# TSSP.net
KiCad netlist of a schematic drawn in Altium Designer
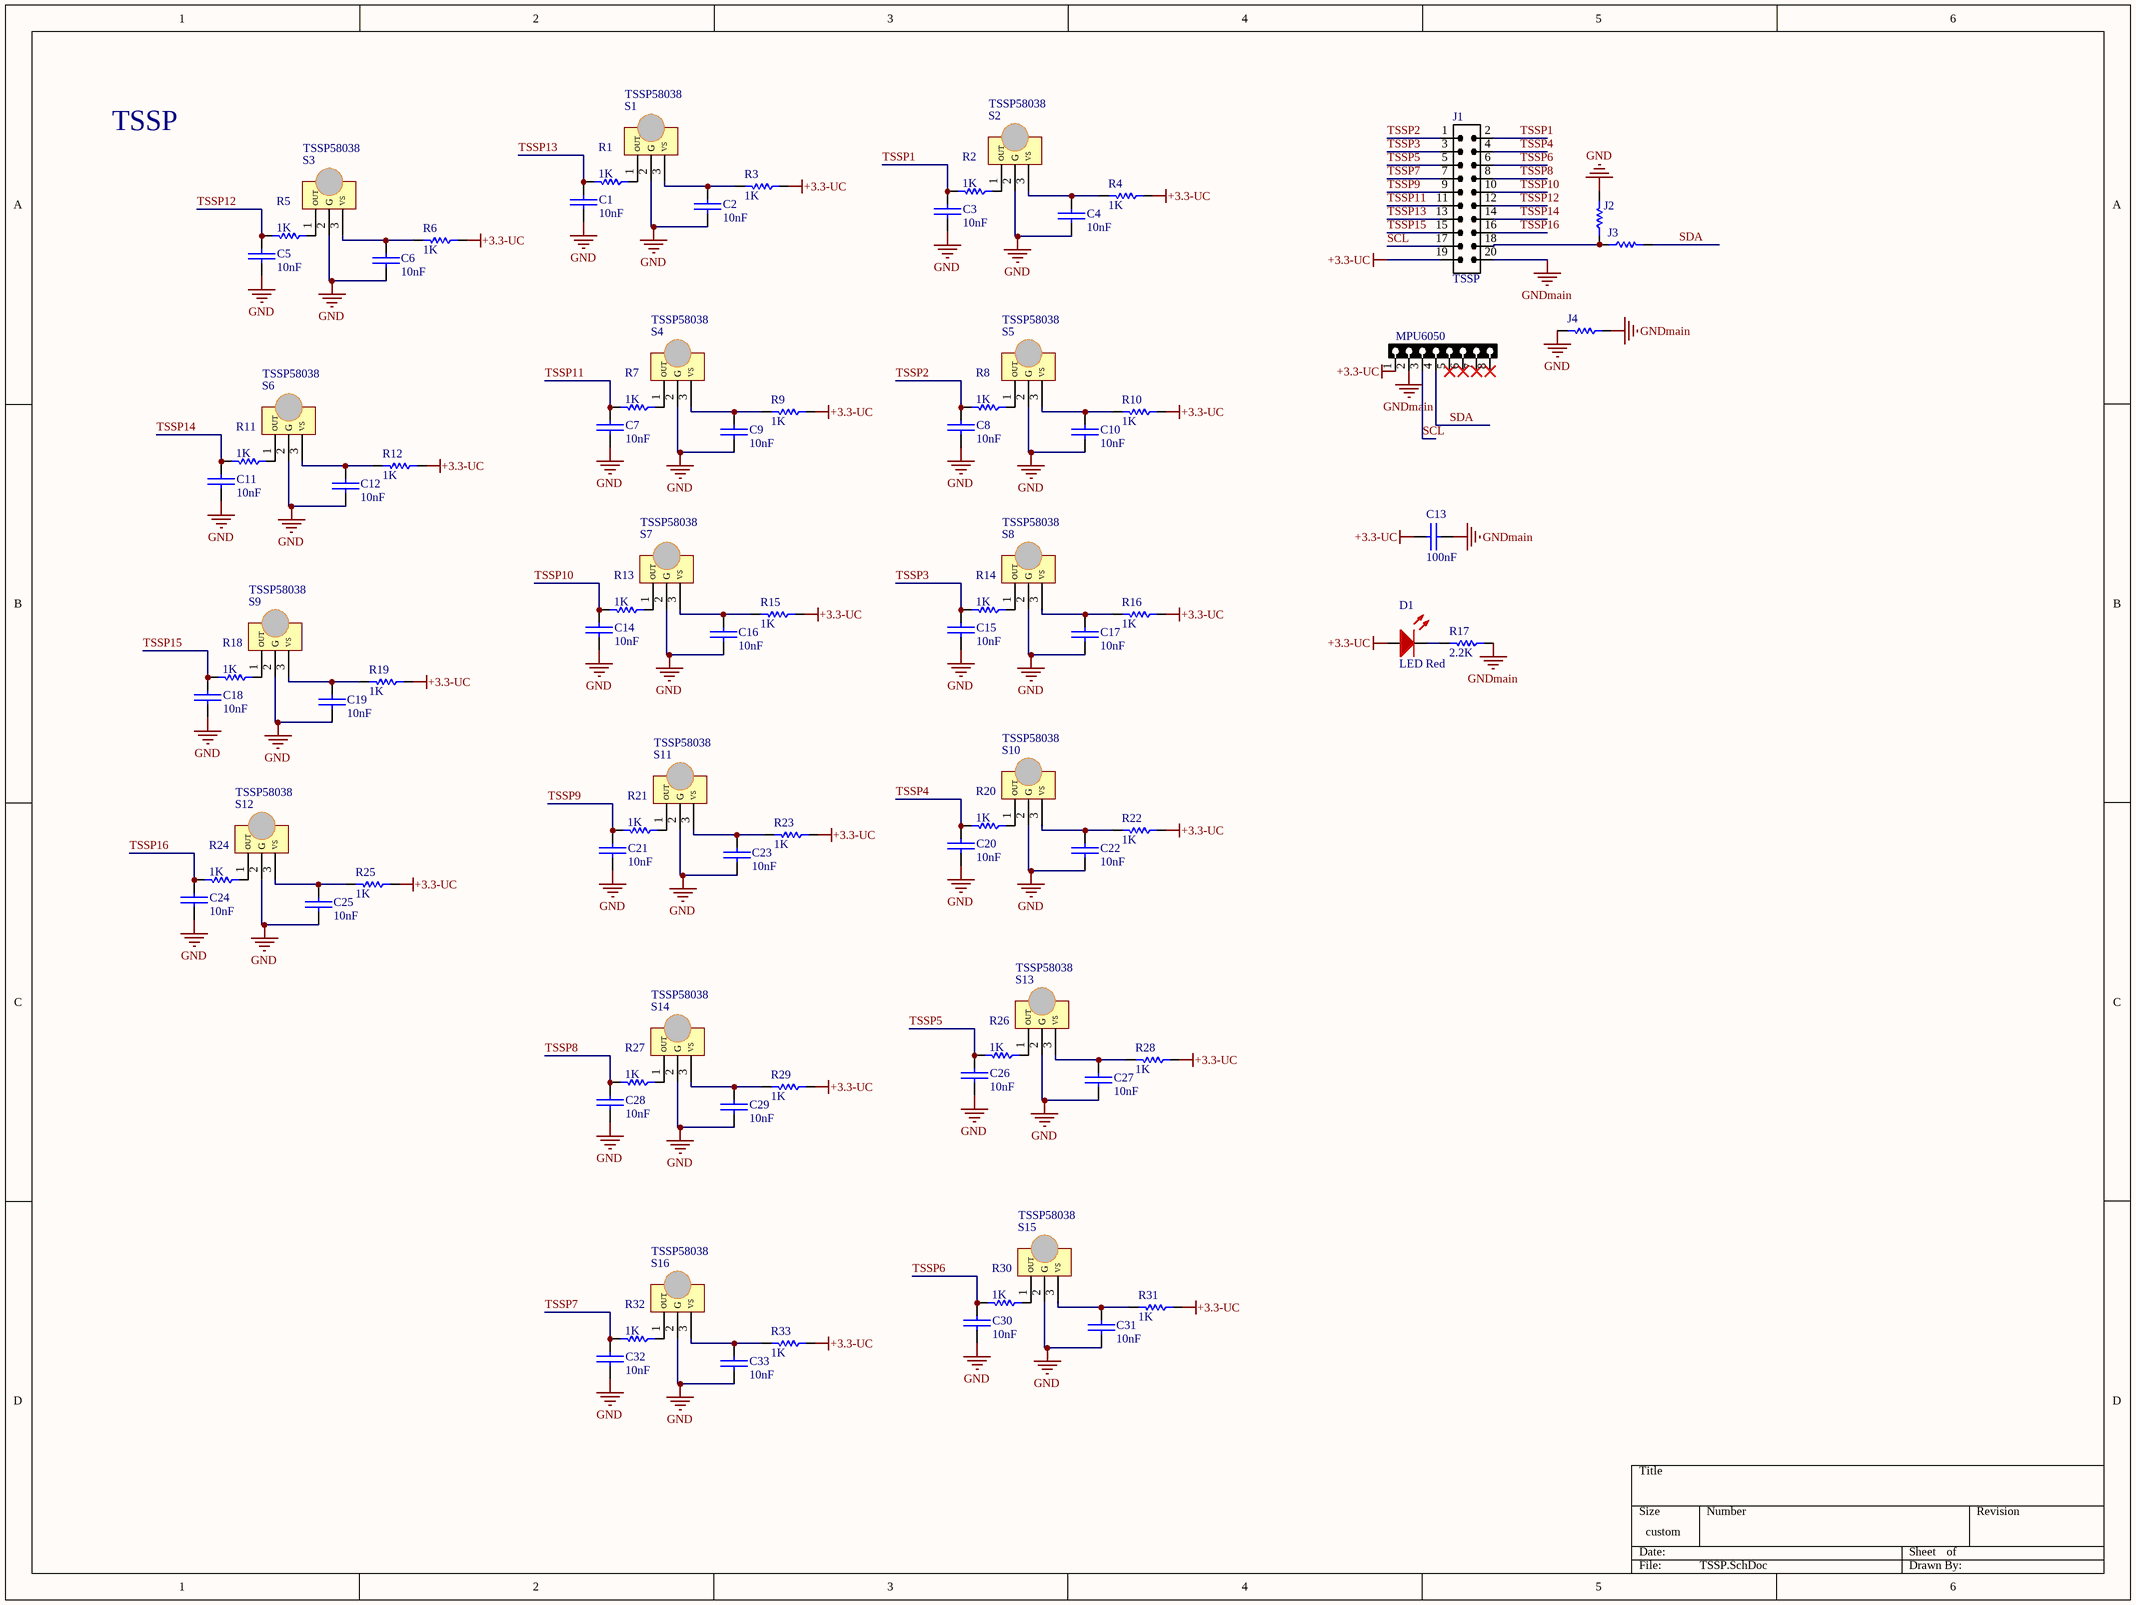
[diagram p0: TSSP.SchDoc]

(export (version "E")
  (design (tool "Eeschema 10.0.6"))
  (components
    (comp (ref "C1")
      (value "10nF")
      (footprint "C0603")
      (description "Bipolar Capacitor")
      (fields (field (name "VOLTAGE") "100V") (field (name "DESIGNER") "Saeid Jorablo"))
      (libsource (lib "My Library") (part "Cap-Bipolar"))
    )
    (comp (ref "C2")
      (value "10nF")
      (footprint "C0603")
      (description "Bipolar Capacitor")
      (fields (field (name "VOLTAGE") "100V") (field (name "DESIGNER") "Saeid Jorablo"))
      (libsource (lib "My Library") (part "Cap-Bipolar"))
    )
    (comp (ref "C3")
      (value "10nF")
      (footprint "C0603")
      (description "Bipolar Capacitor")
      (fields (field (name "VOLTAGE") "100V") (field (name "DESIGNER") "Saeid Jorablo"))
      (libsource (lib "My Library") (part "Cap-Bipolar"))
    )
    (comp (ref "C4")
      (value "10nF")
      (footprint "C0603")
      (description "Bipolar Capacitor")
      (fields (field (name "VOLTAGE") "100V") (field (name "DESIGNER") "Saeid Jorablo"))
      (libsource (lib "My Library") (part "Cap-Bipolar"))
    )
    (comp (ref "C5")
      (value "10nF")
      (footprint "C0603")
      (description "Bipolar Capacitor")
      (fields (field (name "VOLTAGE") "100V") (field (name "DESIGNER") "Saeid Jorablo"))
      (libsource (lib "My Library") (part "Cap-Bipolar"))
    )
    (comp (ref "C6")
      (value "10nF")
      (footprint "C0603")
      (description "Bipolar Capacitor")
      (fields (field (name "VOLTAGE") "100V") (field (name "DESIGNER") "Saeid Jorablo"))
      (libsource (lib "My Library") (part "Cap-Bipolar"))
    )
    (comp (ref "C7")
      (value "10nF")
      (footprint "C0603")
      (description "Bipolar Capacitor")
      (fields (field (name "VOLTAGE") "100V") (field (name "DESIGNER") "Saeid Jorablo"))
      (libsource (lib "My Library") (part "Cap-Bipolar"))
    )
    (comp (ref "C8")
      (value "10nF")
      (footprint "C0603")
      (description "Bipolar Capacitor")
      (fields (field (name "VOLTAGE") "100V") (field (name "DESIGNER") "Saeid Jorablo"))
      (libsource (lib "My Library") (part "Cap-Bipolar"))
    )
    (comp (ref "C9")
      (value "10nF")
      (footprint "C0603")
      (description "Bipolar Capacitor")
      (fields (field (name "VOLTAGE") "100V") (field (name "DESIGNER") "Saeid Jorablo"))
      (libsource (lib "My Library") (part "Cap-Bipolar"))
    )
    (comp (ref "C10")
      (value "10nF")
      (footprint "C0603")
      (description "Bipolar Capacitor")
      (fields (field (name "VOLTAGE") "100V") (field (name "DESIGNER") "Saeid Jorablo"))
      (libsource (lib "My Library") (part "Cap-Bipolar"))
    )
    (comp (ref "C11")
      (value "10nF")
      (footprint "C0603")
      (description "Bipolar Capacitor")
      (fields (field (name "VOLTAGE") "100V") (field (name "DESIGNER") "Saeid Jorablo"))
      (libsource (lib "My Library") (part "Cap-Bipolar"))
    )
    (comp (ref "C12")
      (value "10nF")
      (footprint "C0603")
      (description "Bipolar Capacitor")
      (fields (field (name "VOLTAGE") "100V") (field (name "DESIGNER") "Saeid Jorablo"))
      (libsource (lib "My Library") (part "Cap-Bipolar"))
    )
    (comp (ref "C13")
      (value "100nF")
      (footprint "SMD_CAP_0805")
      (description "Bipolar Capacitor")
      (fields (field (name "VOLTAGE") "100V") (field (name "DESIGNER") "Saeid Jorablo"))
      (libsource (lib "My Library") (part "Cap-Bipolar"))
    )
    (comp (ref "C14")
      (value "10nF")
      (footprint "C0603")
      (description "Bipolar Capacitor")
      (fields (field (name "VOLTAGE") "100V") (field (name "DESIGNER") "Saeid Jorablo"))
      (libsource (lib "My Library") (part "Cap-Bipolar"))
    )
    (comp (ref "C15")
      (value "10nF")
      (footprint "C0603")
      (description "Bipolar Capacitor")
      (fields (field (name "VOLTAGE") "100V") (field (name "DESIGNER") "Saeid Jorablo"))
      (libsource (lib "My Library") (part "Cap-Bipolar"))
    )
    (comp (ref "C16")
      (value "10nF")
      (footprint "C0603")
      (description "Bipolar Capacitor")
      (fields (field (name "VOLTAGE") "100V") (field (name "DESIGNER") "Saeid Jorablo"))
      (libsource (lib "My Library") (part "Cap-Bipolar"))
    )
    (comp (ref "C17")
      (value "10nF")
      (footprint "C0603")
      (description "Bipolar Capacitor")
      (fields (field (name "VOLTAGE") "100V") (field (name "DESIGNER") "Saeid Jorablo"))
      (libsource (lib "My Library") (part "Cap-Bipolar"))
    )
    (comp (ref "C18")
      (value "10nF")
      (footprint "C0603")
      (description "Bipolar Capacitor")
      (fields (field (name "VOLTAGE") "100V") (field (name "DESIGNER") "Saeid Jorablo"))
      (libsource (lib "My Library") (part "Cap-Bipolar"))
    )
    (comp (ref "C19")
      (value "10nF")
      (footprint "C0603")
      (description "Bipolar Capacitor")
      (fields (field (name "VOLTAGE") "100V") (field (name "DESIGNER") "Saeid Jorablo"))
      (libsource (lib "My Library") (part "Cap-Bipolar"))
    )
    (comp (ref "C20")
      (value "10nF")
      (footprint "C0603")
      (description "Bipolar Capacitor")
      (fields (field (name "VOLTAGE") "100V") (field (name "DESIGNER") "Saeid Jorablo"))
      (libsource (lib "My Library") (part "Cap-Bipolar"))
    )
    (comp (ref "C21")
      (value "10nF")
      (footprint "C0603")
      (description "Bipolar Capacitor")
      (fields (field (name "VOLTAGE") "100V") (field (name "DESIGNER") "Saeid Jorablo"))
      (libsource (lib "My Library") (part "Cap-Bipolar"))
    )
    (comp (ref "C22")
      (value "10nF")
      (footprint "C0603")
      (description "Bipolar Capacitor")
      (fields (field (name "VOLTAGE") "100V") (field (name "DESIGNER") "Saeid Jorablo"))
      (libsource (lib "My Library") (part "Cap-Bipolar"))
    )
    (comp (ref "C23")
      (value "10nF")
      (footprint "C0603")
      (description "Bipolar Capacitor")
      (fields (field (name "VOLTAGE") "100V") (field (name "DESIGNER") "Saeid Jorablo"))
      (libsource (lib "My Library") (part "Cap-Bipolar"))
    )
    (comp (ref "C24")
      (value "10nF")
      (footprint "C0603")
      (description "Bipolar Capacitor")
      (fields (field (name "VOLTAGE") "100V") (field (name "DESIGNER") "Saeid Jorablo"))
      (libsource (lib "My Library") (part "Cap-Bipolar"))
    )
    (comp (ref "C25")
      (value "10nF")
      (footprint "C0603")
      (description "Bipolar Capacitor")
      (fields (field (name "VOLTAGE") "100V") (field (name "DESIGNER") "Saeid Jorablo"))
      (libsource (lib "My Library") (part "Cap-Bipolar"))
    )
    (comp (ref "C26")
      (value "10nF")
      (footprint "C0603")
      (description "Bipolar Capacitor")
      (fields (field (name "VOLTAGE") "100V") (field (name "DESIGNER") "Saeid Jorablo"))
      (libsource (lib "My Library") (part "Cap-Bipolar"))
    )
    (comp (ref "C27")
      (value "10nF")
      (footprint "C0603")
      (description "Bipolar Capacitor")
      (fields (field (name "VOLTAGE") "100V") (field (name "DESIGNER") "Saeid Jorablo"))
      (libsource (lib "My Library") (part "Cap-Bipolar"))
    )
    (comp (ref "C28")
      (value "10nF")
      (footprint "C0603")
      (description "Bipolar Capacitor")
      (fields (field (name "VOLTAGE") "100V") (field (name "DESIGNER") "Saeid Jorablo"))
      (libsource (lib "My Library") (part "Cap-Bipolar"))
    )
    (comp (ref "C29")
      (value "10nF")
      (footprint "C0603")
      (description "Bipolar Capacitor")
      (fields (field (name "VOLTAGE") "100V") (field (name "DESIGNER") "Saeid Jorablo"))
      (libsource (lib "My Library") (part "Cap-Bipolar"))
    )
    (comp (ref "C30")
      (value "10nF")
      (footprint "C0603")
      (description "Bipolar Capacitor")
      (fields (field (name "VOLTAGE") "100V") (field (name "DESIGNER") "Saeid Jorablo"))
      (libsource (lib "My Library") (part "Cap-Bipolar"))
    )
    (comp (ref "C31")
      (value "10nF")
      (footprint "C0603")
      (description "Bipolar Capacitor")
      (fields (field (name "VOLTAGE") "100V") (field (name "DESIGNER") "Saeid Jorablo"))
      (libsource (lib "My Library") (part "Cap-Bipolar"))
    )
    (comp (ref "C32")
      (value "10nF")
      (footprint "C0603")
      (description "Bipolar Capacitor")
      (fields (field (name "VOLTAGE") "100V") (field (name "DESIGNER") "Saeid Jorablo"))
      (libsource (lib "My Library") (part "Cap-Bipolar"))
    )
    (comp (ref "C33")
      (value "10nF")
      (footprint "C0603")
      (description "Bipolar Capacitor")
      (fields (field (name "VOLTAGE") "100V") (field (name "DESIGNER") "Saeid Jorablo"))
      (libsource (lib "My Library") (part "Cap-Bipolar"))
    )
    (comp (ref "D1")
      (value "LED Red")
      (footprint "LED_Red_1206")
      (libsource (lib "AYRIC Library") (part "LED Red"))
    )
    (comp (ref "J1")
      (value "TSSP")
      (footprint "IDC_2X10")
      (description "CONN, IDC, Male, pitch: 2.54mm, 20POS")
      (libsource (lib "conn_header_idc") (part "IDC_2X10"))
    )
    (comp (ref "J2")
      (value "~")
      (footprint "RES 0805 (2012X06L)")
      (description "Resistor")
      (libsource (lib "My Library") (part "Resistor"))
    )
    (comp (ref "J3")
      (value "~")
      (footprint "RES 0805 (2012X06L)")
      (description "Resistor")
      (libsource (lib "My Library") (part "Resistor"))
    )
    (comp (ref "J4")
      (value "~")
      (footprint "RES 0805 (2012X06L)")
      (description "Resistor")
      (libsource (lib "My Library") (part "Resistor"))
    )
    (comp (ref "MPU6050")
      (value "HDRF8")
      (footprint "HDR_F_1X8")
      (description "CONN, HEADER, Female, pitch: 2.54mm, 8POS")
      (libsource (lib "conn_header") (part "HDR_F_1X8"))
    )
    (comp (ref "R1")
      (value "1K")
      (footprint "RES 0603 (1608X06L)")
      (description "Resistor")
      (libsource (lib "My Library") (part "Resistor"))
    )
    (comp (ref "R2")
      (value "1K")
      (footprint "RES 0603 (1608X06L)")
      (description "Resistor")
      (libsource (lib "My Library") (part "Resistor"))
    )
    (comp (ref "R3")
      (value "1K")
      (footprint "RES 0603 (1608X06L)")
      (description "Resistor")
      (libsource (lib "My Library") (part "Resistor"))
    )
    (comp (ref "R4")
      (value "1K")
      (footprint "RES 0603 (1608X06L)")
      (description "Resistor")
      (libsource (lib "My Library") (part "Resistor"))
    )
    (comp (ref "R5")
      (value "1K")
      (footprint "RES 0603 (1608X06L)")
      (description "Resistor")
      (libsource (lib "My Library") (part "Resistor"))
    )
    (comp (ref "R6")
      (value "1K")
      (footprint "RES 0603 (1608X06L)")
      (description "Resistor")
      (libsource (lib "My Library") (part "Resistor"))
    )
    (comp (ref "R7")
      (value "1K")
      (footprint "RES 0603 (1608X06L)")
      (description "Resistor")
      (libsource (lib "My Library") (part "Resistor"))
    )
    (comp (ref "R8")
      (value "1K")
      (footprint "RES 0603 (1608X06L)")
      (description "Resistor")
      (libsource (lib "My Library") (part "Resistor"))
    )
    (comp (ref "R9")
      (value "1K")
      (footprint "RES 0603 (1608X06L)")
      (description "Resistor")
      (libsource (lib "My Library") (part "Resistor"))
    )
    (comp (ref "R10")
      (value "1K")
      (footprint "RES 0603 (1608X06L)")
      (description "Resistor")
      (libsource (lib "My Library") (part "Resistor"))
    )
    (comp (ref "R11")
      (value "1K")
      (footprint "RES 0603 (1608X06L)")
      (description "Resistor")
      (libsource (lib "My Library") (part "Resistor"))
    )
    (comp (ref "R12")
      (value "1K")
      (footprint "RES 0603 (1608X06L)")
      (description "Resistor")
      (libsource (lib "My Library") (part "Resistor"))
    )
    (comp (ref "R13")
      (value "1K")
      (footprint "RES 0603 (1608X06L)")
      (description "Resistor")
      (libsource (lib "My Library") (part "Resistor"))
    )
    (comp (ref "R14")
      (value "1K")
      (footprint "RES 0603 (1608X06L)")
      (description "Resistor")
      (libsource (lib "My Library") (part "Resistor"))
    )
    (comp (ref "R15")
      (value "1K")
      (footprint "RES 0603 (1608X06L)")
      (description "Resistor")
      (libsource (lib "My Library") (part "Resistor"))
    )
    (comp (ref "R16")
      (value "1K")
      (footprint "RES 0603 (1608X06L)")
      (description "Resistor")
      (libsource (lib "My Library") (part "Resistor"))
    )
    (comp (ref "R17")
      (value "2.2K")
      (footprint "RES 0805 (2012X06L)")
      (description "Resistor")
      (libsource (lib "My Library") (part "Resistor"))
    )
    (comp (ref "R18")
      (value "1K")
      (footprint "RES 0603 (1608X06L)")
      (description "Resistor")
      (libsource (lib "My Library") (part "Resistor"))
    )
    (comp (ref "R19")
      (value "1K")
      (footprint "RES 0603 (1608X06L)")
      (description "Resistor")
      (libsource (lib "My Library") (part "Resistor"))
    )
    (comp (ref "R20")
      (value "1K")
      (footprint "RES 0603 (1608X06L)")
      (description "Resistor")
      (libsource (lib "My Library") (part "Resistor"))
    )
    (comp (ref "R21")
      (value "1K")
      (footprint "RES 0603 (1608X06L)")
      (description "Resistor")
      (libsource (lib "My Library") (part "Resistor"))
    )
    (comp (ref "R22")
      (value "1K")
      (footprint "RES 0603 (1608X06L)")
      (description "Resistor")
      (libsource (lib "My Library") (part "Resistor"))
    )
    (comp (ref "R23")
      (value "1K")
      (footprint "RES 0603 (1608X06L)")
      (description "Resistor")
      (libsource (lib "My Library") (part "Resistor"))
    )
    (comp (ref "R24")
      (value "1K")
      (footprint "RES 0603 (1608X06L)")
      (description "Resistor")
      (libsource (lib "My Library") (part "Resistor"))
    )
    (comp (ref "R25")
      (value "1K")
      (footprint "RES 0603 (1608X06L)")
      (description "Resistor")
      (libsource (lib "My Library") (part "Resistor"))
    )
    (comp (ref "R26")
      (value "1K")
      (footprint "RES 0603 (1608X06L)")
      (description "Resistor")
      (libsource (lib "My Library") (part "Resistor"))
    )
    (comp (ref "R27")
      (value "1K")
      (footprint "RES 0603 (1608X06L)")
      (description "Resistor")
      (libsource (lib "My Library") (part "Resistor"))
    )
    (comp (ref "R28")
      (value "1K")
      (footprint "RES 0603 (1608X06L)")
      (description "Resistor")
      (libsource (lib "My Library") (part "Resistor"))
    )
    (comp (ref "R29")
      (value "1K")
      (footprint "RES 0603 (1608X06L)")
      (description "Resistor")
      (libsource (lib "My Library") (part "Resistor"))
    )
    (comp (ref "R30")
      (value "1K")
      (footprint "RES 0603 (1608X06L)")
      (description "Resistor")
      (libsource (lib "My Library") (part "Resistor"))
    )
    (comp (ref "R31")
      (value "1K")
      (footprint "RES 0603 (1608X06L)")
      (description "Resistor")
      (libsource (lib "My Library") (part "Resistor"))
    )
    (comp (ref "R32")
      (value "1K")
      (footprint "RES 0603 (1608X06L)")
      (description "Resistor")
      (libsource (lib "My Library") (part "Resistor"))
    )
    (comp (ref "R33")
      (value "1K")
      (footprint "RES 0603 (1608X06L)")
      (description "Resistor")
      (libsource (lib "My Library") (part "Resistor"))
    )
    (comp (ref "S1") (value "TSSP58038") (footprint "TSSP58038") (libsource (lib "MA01") (part "TSSP58038")))
    (comp (ref "S2") (value "TSSP58038") (footprint "TSSP58038") (libsource (lib "MA01") (part "TSSP58038")))
    (comp (ref "S3") (value "TSSP58038") (footprint "TSSP58038") (libsource (lib "MA01") (part "TSSP58038")))
    (comp (ref "S4") (value "TSSP58038") (footprint "TSSP58038") (libsource (lib "MA01") (part "TSSP58038")))
    (comp (ref "S5") (value "TSSP58038") (footprint "TSSP58038") (libsource (lib "MA01") (part "TSSP58038")))
    (comp (ref "S6") (value "TSSP58038") (footprint "TSSP58038") (libsource (lib "MA01") (part "TSSP58038")))
    (comp (ref "S7") (value "TSSP58038") (footprint "TSSP58038") (libsource (lib "MA01") (part "TSSP58038")))
    (comp (ref "S8") (value "TSSP58038") (footprint "TSSP58038") (libsource (lib "MA01") (part "TSSP58038")))
    (comp (ref "S9") (value "TSSP58038") (footprint "TSSP58038") (libsource (lib "MA01") (part "TSSP58038")))
    (comp (ref "S10") (value "TSSP58038") (footprint "TSSP58038") (libsource (lib "MA01") (part "TSSP58038")))
    (comp (ref "S11") (value "TSSP58038") (footprint "TSSP58038") (libsource (lib "MA01") (part "TSSP58038")))
    (comp (ref "S12") (value "TSSP58038") (footprint "TSSP58038") (libsource (lib "MA01") (part "TSSP58038")))
    (comp (ref "S13") (value "TSSP58038") (footprint "TSSP58038") (libsource (lib "MA01") (part "TSSP58038")))
    (comp (ref "S14") (value "TSSP58038") (footprint "TSSP58038") (libsource (lib "MA01") (part "TSSP58038")))
    (comp (ref "S15") (value "TSSP58038") (footprint "TSSP58038") (libsource (lib "MA01") (part "TSSP58038")))
    (comp (ref "S16") (value "TSSP58038") (footprint "TSSP58038") (libsource (lib "MA01") (part "TSSP58038")))
  )
  (nets
    (net (code "1") (name "+3.3-UC") (class "Default")
      (node (ref "C13") (pin "1") (pinfunction "+_1") (pintype "passive"))
      (node (ref "D1") (pin "1") (pinfunction "A_1") (pintype "passive"))
      (node (ref "J1") (pin "19") (pinfunction "19_19") (pintype "passive"))
      (node (ref "MPU6050") (pin "1") (pinfunction "1_1") (pintype "passive"))
      (node (ref "R10") (pin "1") (pinfunction "1_1") (pintype "passive"))
      (node (ref "R12") (pin "1") (pinfunction "1_1") (pintype "passive"))
      (node (ref "R15") (pin "1") (pinfunction "1_1") (pintype "passive"))
      (node (ref "R16") (pin "1") (pinfunction "1_1") (pintype "passive"))
      (node (ref "R19") (pin "1") (pinfunction "1_1") (pintype "passive"))
      (node (ref "R22") (pin "1") (pinfunction "1_1") (pintype "passive"))
      (node (ref "R23") (pin "1") (pinfunction "1_1") (pintype "passive"))
      (node (ref "R25") (pin "1") (pinfunction "1_1") (pintype "passive"))
      (node (ref "R28") (pin "1") (pinfunction "1_1") (pintype "passive"))
      (node (ref "R29") (pin "1") (pinfunction "1_1") (pintype "passive"))
      (node (ref "R3") (pin "1") (pinfunction "1_1") (pintype "passive"))
      (node (ref "R31") (pin "1") (pinfunction "1_1") (pintype "passive"))
      (node (ref "R33") (pin "1") (pinfunction "1_1") (pintype "passive"))
      (node (ref "R4") (pin "1") (pinfunction "1_1") (pintype "passive"))
      (node (ref "R6") (pin "1") (pinfunction "1_1") (pintype "passive"))
      (node (ref "R9") (pin "1") (pinfunction "1_1") (pintype "passive"))
    )
    (net (code "2") (name "/SCL") (class "Default")
      (node (ref "J1") (pin "17") (pinfunction "17_17") (pintype "passive"))
      (node (ref "MPU6050") (pin "3") (pinfunction "3_3") (pintype "passive"))
    )
    (net (code "3") (name "/SDA") (class "Default")
      (node (ref "J3") (pin "2") (pinfunction "2_2") (pintype "passive"))
      (node (ref "MPU6050") (pin "4") (pinfunction "4_4") (pintype "passive"))
    )
    (net (code "4") (name "/TSSP1") (class "Default")
      (node (ref "C3") (pin "1") (pinfunction "+_1") (pintype "passive"))
      (node (ref "J1") (pin "2") (pinfunction "2_2") (pintype "passive"))
      (node (ref "R2") (pin "2") (pinfunction "2_2") (pintype "passive"))
    )
    (net (code "5") (name "/TSSP2") (class "Default")
      (node (ref "C8") (pin "1") (pinfunction "+_1") (pintype "passive"))
      (node (ref "J1") (pin "1") (pinfunction "1_1") (pintype "passive"))
      (node (ref "R8") (pin "2") (pinfunction "2_2") (pintype "passive"))
    )
    (net (code "6") (name "/TSSP3") (class "Default")
      (node (ref "C15") (pin "1") (pinfunction "+_1") (pintype "passive"))
      (node (ref "J1") (pin "3") (pinfunction "3_3") (pintype "passive"))
      (node (ref "R14") (pin "2") (pinfunction "2_2") (pintype "passive"))
    )
    (net (code "7") (name "/TSSP4") (class "Default")
      (node (ref "C20") (pin "1") (pinfunction "+_1") (pintype "passive"))
      (node (ref "J1") (pin "4") (pinfunction "4_4") (pintype "passive"))
      (node (ref "R20") (pin "2") (pinfunction "2_2") (pintype "passive"))
    )
    (net (code "8") (name "/TSSP5") (class "Default")
      (node (ref "C26") (pin "1") (pinfunction "+_1") (pintype "passive"))
      (node (ref "J1") (pin "5") (pinfunction "5_5") (pintype "passive"))
      (node (ref "R26") (pin "2") (pinfunction "2_2") (pintype "passive"))
    )
    (net (code "9") (name "/TSSP6") (class "Default")
      (node (ref "C30") (pin "1") (pinfunction "+_1") (pintype "passive"))
      (node (ref "J1") (pin "6") (pinfunction "6_6") (pintype "passive"))
      (node (ref "R30") (pin "2") (pinfunction "2_2") (pintype "passive"))
    )
    (net (code "10") (name "/TSSP7") (class "Default")
      (node (ref "C32") (pin "1") (pinfunction "+_1") (pintype "passive"))
      (node (ref "J1") (pin "7") (pinfunction "7_7") (pintype "passive"))
      (node (ref "R32") (pin "2") (pinfunction "2_2") (pintype "passive"))
    )
    (net (code "11") (name "/TSSP8") (class "Default")
      (node (ref "C28") (pin "1") (pinfunction "+_1") (pintype "passive"))
      (node (ref "J1") (pin "8") (pinfunction "8_8") (pintype "passive"))
      (node (ref "R27") (pin "2") (pinfunction "2_2") (pintype "passive"))
    )
    (net (code "12") (name "/TSSP9") (class "Default")
      (node (ref "C21") (pin "1") (pinfunction "+_1") (pintype "passive"))
      (node (ref "J1") (pin "9") (pinfunction "9_9") (pintype "passive"))
      (node (ref "R21") (pin "2") (pinfunction "2_2") (pintype "passive"))
    )
    (net (code "13") (name "/TSSP10") (class "Default")
      (node (ref "C14") (pin "1") (pinfunction "+_1") (pintype "passive"))
      (node (ref "J1") (pin "10") (pinfunction "10_10") (pintype "passive"))
      (node (ref "R13") (pin "2") (pinfunction "2_2") (pintype "passive"))
    )
    (net (code "14") (name "/TSSP11") (class "Default")
      (node (ref "C7") (pin "1") (pinfunction "+_1") (pintype "passive"))
      (node (ref "J1") (pin "11") (pinfunction "11_11") (pintype "passive"))
      (node (ref "R7") (pin "2") (pinfunction "2_2") (pintype "passive"))
    )
    (net (code "15") (name "/TSSP12") (class "Default")
      (node (ref "C5") (pin "1") (pinfunction "+_1") (pintype "passive"))
      (node (ref "J1") (pin "12") (pinfunction "12_12") (pintype "passive"))
      (node (ref "R5") (pin "2") (pinfunction "2_2") (pintype "passive"))
    )
    (net (code "16") (name "/TSSP13") (class "Default")
      (node (ref "C1") (pin "1") (pinfunction "+_1") (pintype "passive"))
      (node (ref "J1") (pin "13") (pinfunction "13_13") (pintype "passive"))
      (node (ref "R1") (pin "2") (pinfunction "2_2") (pintype "passive"))
    )
    (net (code "17") (name "/TSSP14") (class "Default")
      (node (ref "C11") (pin "1") (pinfunction "+_1") (pintype "passive"))
      (node (ref "J1") (pin "14") (pinfunction "14_14") (pintype "passive"))
      (node (ref "R11") (pin "2") (pinfunction "2_2") (pintype "passive"))
    )
    (net (code "18") (name "/TSSP15") (class "Default")
      (node (ref "C18") (pin "1") (pinfunction "+_1") (pintype "passive"))
      (node (ref "J1") (pin "15") (pinfunction "15_15") (pintype "passive"))
      (node (ref "R18") (pin "2") (pinfunction "2_2") (pintype "passive"))
    )
    (net (code "19") (name "/TSSP16") (class "Default")
      (node (ref "C24") (pin "1") (pinfunction "+_1") (pintype "passive"))
      (node (ref "J1") (pin "16") (pinfunction "16_16") (pintype "passive"))
      (node (ref "R24") (pin "2") (pinfunction "2_2") (pintype "passive"))
    )
    (net (code "20") (name "GND") (class "Default")
      (node (ref "C1") (pin "2") (pinfunction "-_2") (pintype "passive"))
      (node (ref "C10") (pin "2") (pinfunction "-_2") (pintype "passive"))
      (node (ref "C11") (pin "2") (pinfunction "-_2") (pintype "passive"))
      (node (ref "C12") (pin "2") (pinfunction "-_2") (pintype "passive"))
      (node (ref "C14") (pin "2") (pinfunction "-_2") (pintype "passive"))
      (node (ref "C15") (pin "2") (pinfunction "-_2") (pintype "passive"))
      (node (ref "C16") (pin "2") (pinfunction "-_2") (pintype "passive"))
      (node (ref "C17") (pin "2") (pinfunction "-_2") (pintype "passive"))
      (node (ref "C18") (pin "2") (pinfunction "-_2") (pintype "passive"))
      (node (ref "C19") (pin "2") (pinfunction "-_2") (pintype "passive"))
      (node (ref "C2") (pin "2") (pinfunction "-_2") (pintype "passive"))
      (node (ref "C20") (pin "2") (pinfunction "-_2") (pintype "passive"))
      (node (ref "C21") (pin "2") (pinfunction "-_2") (pintype "passive"))
      (node (ref "C22") (pin "2") (pinfunction "-_2") (pintype "passive"))
      (node (ref "C23") (pin "2") (pinfunction "-_2") (pintype "passive"))
      (node (ref "C24") (pin "2") (pinfunction "-_2") (pintype "passive"))
      (node (ref "C25") (pin "2") (pinfunction "-_2") (pintype "passive"))
      (node (ref "C26") (pin "2") (pinfunction "-_2") (pintype "passive"))
      (node (ref "C27") (pin "2") (pinfunction "-_2") (pintype "passive"))
      (node (ref "C28") (pin "2") (pinfunction "-_2") (pintype "passive"))
      (node (ref "C29") (pin "2") (pinfunction "-_2") (pintype "passive"))
      (node (ref "C3") (pin "2") (pinfunction "-_2") (pintype "passive"))
      (node (ref "C30") (pin "2") (pinfunction "-_2") (pintype "passive"))
      (node (ref "C31") (pin "2") (pinfunction "-_2") (pintype "passive"))
      (node (ref "C32") (pin "2") (pinfunction "-_2") (pintype "passive"))
      (node (ref "C33") (pin "2") (pinfunction "-_2") (pintype "passive"))
      (node (ref "C4") (pin "2") (pinfunction "-_2") (pintype "passive"))
      (node (ref "C5") (pin "2") (pinfunction "-_2") (pintype "passive"))
      (node (ref "C6") (pin "2") (pinfunction "-_2") (pintype "passive"))
      (node (ref "C7") (pin "2") (pinfunction "-_2") (pintype "passive"))
      (node (ref "C8") (pin "2") (pinfunction "-_2") (pintype "passive"))
      (node (ref "C9") (pin "2") (pinfunction "-_2") (pintype "passive"))
      (node (ref "J2") (pin "2") (pinfunction "2_2") (pintype "passive"))
      (node (ref "J4") (pin "2") (pinfunction "2_2") (pintype "passive"))
      (node (ref "S1") (pin "2") (pinfunction "G_2") (pintype "passive"))
      (node (ref "S10") (pin "2") (pinfunction "G_2") (pintype "passive"))
      (node (ref "S11") (pin "2") (pinfunction "G_2") (pintype "passive"))
      (node (ref "S12") (pin "2") (pinfunction "G_2") (pintype "passive"))
      (node (ref "S13") (pin "2") (pinfunction "G_2") (pintype "passive"))
      (node (ref "S14") (pin "2") (pinfunction "G_2") (pintype "passive"))
      (node (ref "S15") (pin "2") (pinfunction "G_2") (pintype "passive"))
      (node (ref "S16") (pin "2") (pinfunction "G_2") (pintype "passive"))
      (node (ref "S2") (pin "2") (pinfunction "G_2") (pintype "passive"))
      (node (ref "S3") (pin "2") (pinfunction "G_2") (pintype "passive"))
      (node (ref "S4") (pin "2") (pinfunction "G_2") (pintype "passive"))
      (node (ref "S5") (pin "2") (pinfunction "G_2") (pintype "passive"))
      (node (ref "S6") (pin "2") (pinfunction "G_2") (pintype "passive"))
      (node (ref "S7") (pin "2") (pinfunction "G_2") (pintype "passive"))
      (node (ref "S8") (pin "2") (pinfunction "G_2") (pintype "passive"))
      (node (ref "S9") (pin "2") (pinfunction "G_2") (pintype "passive"))
    )
    (net (code "21") (name "GNDmain") (class "Default")
      (node (ref "C13") (pin "2") (pinfunction "-_2") (pintype "passive"))
      (node (ref "J1") (pin "20") (pinfunction "20_20") (pintype "passive"))
      (node (ref "J4") (pin "1") (pinfunction "1_1") (pintype "passive"))
      (node (ref "MPU6050") (pin "2") (pinfunction "2_2") (pintype "passive"))
      (node (ref "R17") (pin "1") (pinfunction "1_1") (pintype "passive"))
    )
    (net (code "22") (name "Net-(C2-+)") (class "Default")
      (node (ref "C2") (pin "1") (pinfunction "+_1") (pintype "passive"))
      (node (ref "R3") (pin "2") (pinfunction "2_2") (pintype "passive"))
      (node (ref "S1") (pin "3") (pinfunction "VS_3") (pintype "passive"))
    )
    (net (code "23") (name "Net-(C4-+)") (class "Default")
      (node (ref "C4") (pin "1") (pinfunction "+_1") (pintype "passive"))
      (node (ref "R4") (pin "2") (pinfunction "2_2") (pintype "passive"))
      (node (ref "S2") (pin "3") (pinfunction "VS_3") (pintype "passive"))
    )
    (net (code "24") (name "Net-(C6-+)") (class "Default")
      (node (ref "C6") (pin "1") (pinfunction "+_1") (pintype "passive"))
      (node (ref "R6") (pin "2") (pinfunction "2_2") (pintype "passive"))
      (node (ref "S3") (pin "3") (pinfunction "VS_3") (pintype "passive"))
    )
    (net (code "25") (name "Net-(C9-+)") (class "Default")
      (node (ref "C9") (pin "1") (pinfunction "+_1") (pintype "passive"))
      (node (ref "R9") (pin "2") (pinfunction "2_2") (pintype "passive"))
      (node (ref "S4") (pin "3") (pinfunction "VS_3") (pintype "passive"))
    )
    (net (code "26") (name "Net-(C10-+)") (class "Default")
      (node (ref "C10") (pin "1") (pinfunction "+_1") (pintype "passive"))
      (node (ref "R10") (pin "2") (pinfunction "2_2") (pintype "passive"))
      (node (ref "S5") (pin "3") (pinfunction "VS_3") (pintype "passive"))
    )
    (net (code "27") (name "Net-(C12-+)") (class "Default")
      (node (ref "C12") (pin "1") (pinfunction "+_1") (pintype "passive"))
      (node (ref "R12") (pin "2") (pinfunction "2_2") (pintype "passive"))
      (node (ref "S6") (pin "3") (pinfunction "VS_3") (pintype "passive"))
    )
    (net (code "28") (name "Net-(C16-+)") (class "Default")
      (node (ref "C16") (pin "1") (pinfunction "+_1") (pintype "passive"))
      (node (ref "R15") (pin "2") (pinfunction "2_2") (pintype "passive"))
      (node (ref "S7") (pin "3") (pinfunction "VS_3") (pintype "passive"))
    )
    (net (code "29") (name "Net-(C17-+)") (class "Default")
      (node (ref "C17") (pin "1") (pinfunction "+_1") (pintype "passive"))
      (node (ref "R16") (pin "2") (pinfunction "2_2") (pintype "passive"))
      (node (ref "S8") (pin "3") (pinfunction "VS_3") (pintype "passive"))
    )
    (net (code "30") (name "Net-(C19-+)") (class "Default")
      (node (ref "C19") (pin "1") (pinfunction "+_1") (pintype "passive"))
      (node (ref "R19") (pin "2") (pinfunction "2_2") (pintype "passive"))
      (node (ref "S9") (pin "3") (pinfunction "VS_3") (pintype "passive"))
    )
    (net (code "31") (name "Net-(C22-+)") (class "Default")
      (node (ref "C22") (pin "1") (pinfunction "+_1") (pintype "passive"))
      (node (ref "R22") (pin "2") (pinfunction "2_2") (pintype "passive"))
      (node (ref "S10") (pin "3") (pinfunction "VS_3") (pintype "passive"))
    )
    (net (code "32") (name "Net-(C23-+)") (class "Default")
      (node (ref "C23") (pin "1") (pinfunction "+_1") (pintype "passive"))
      (node (ref "R23") (pin "2") (pinfunction "2_2") (pintype "passive"))
      (node (ref "S11") (pin "3") (pinfunction "VS_3") (pintype "passive"))
    )
    (net (code "33") (name "Net-(C25-+)") (class "Default")
      (node (ref "C25") (pin "1") (pinfunction "+_1") (pintype "passive"))
      (node (ref "R25") (pin "2") (pinfunction "2_2") (pintype "passive"))
      (node (ref "S12") (pin "3") (pinfunction "VS_3") (pintype "passive"))
    )
    (net (code "34") (name "Net-(C27-+)") (class "Default")
      (node (ref "C27") (pin "1") (pinfunction "+_1") (pintype "passive"))
      (node (ref "R28") (pin "2") (pinfunction "2_2") (pintype "passive"))
      (node (ref "S13") (pin "3") (pinfunction "VS_3") (pintype "passive"))
    )
    (net (code "35") (name "Net-(C29-+)") (class "Default")
      (node (ref "C29") (pin "1") (pinfunction "+_1") (pintype "passive"))
      (node (ref "R29") (pin "2") (pinfunction "2_2") (pintype "passive"))
      (node (ref "S14") (pin "3") (pinfunction "VS_3") (pintype "passive"))
    )
    (net (code "36") (name "Net-(C31-+)") (class "Default")
      (node (ref "C31") (pin "1") (pinfunction "+_1") (pintype "passive"))
      (node (ref "R31") (pin "2") (pinfunction "2_2") (pintype "passive"))
      (node (ref "S15") (pin "3") (pinfunction "VS_3") (pintype "passive"))
    )
    (net (code "37") (name "Net-(C33-+)") (class "Default")
      (node (ref "C33") (pin "1") (pinfunction "+_1") (pintype "passive"))
      (node (ref "R33") (pin "2") (pinfunction "2_2") (pintype "passive"))
      (node (ref "S16") (pin "3") (pinfunction "VS_3") (pintype "passive"))
    )
    (net (code "38") (name "Net-(D1-K)") (class "Default")
      (node (ref "D1") (pin "2") (pinfunction "K_2") (pintype "passive"))
      (node (ref "R17") (pin "2") (pinfunction "2_2") (pintype "passive"))
    )
    (net (code "39") (name "Net-(J1-Pad18)") (class "Default")
      (node (ref "J1") (pin "18") (pinfunction "18_18") (pintype "passive"))
      (node (ref "J2") (pin "1") (pinfunction "1_1") (pintype "passive"))
      (node (ref "J3") (pin "1") (pinfunction "1_1") (pintype "passive"))
    )
    (net (code "40") (name "Net-(S1-OUT)") (class "Default")
      (node (ref "R1") (pin "1") (pinfunction "1_1") (pintype "passive"))
      (node (ref "S1") (pin "1") (pinfunction "OUT_1") (pintype "passive"))
    )
    (net (code "41") (name "Net-(S2-OUT)") (class "Default")
      (node (ref "R2") (pin "1") (pinfunction "1_1") (pintype "passive"))
      (node (ref "S2") (pin "1") (pinfunction "OUT_1") (pintype "passive"))
    )
    (net (code "42") (name "Net-(S3-OUT)") (class "Default")
      (node (ref "R5") (pin "1") (pinfunction "1_1") (pintype "passive"))
      (node (ref "S3") (pin "1") (pinfunction "OUT_1") (pintype "passive"))
    )
    (net (code "43") (name "Net-(S4-OUT)") (class "Default")
      (node (ref "R7") (pin "1") (pinfunction "1_1") (pintype "passive"))
      (node (ref "S4") (pin "1") (pinfunction "OUT_1") (pintype "passive"))
    )
    (net (code "44") (name "Net-(S5-OUT)") (class "Default")
      (node (ref "R8") (pin "1") (pinfunction "1_1") (pintype "passive"))
      (node (ref "S5") (pin "1") (pinfunction "OUT_1") (pintype "passive"))
    )
    (net (code "45") (name "Net-(S6-OUT)") (class "Default")
      (node (ref "R11") (pin "1") (pinfunction "1_1") (pintype "passive"))
      (node (ref "S6") (pin "1") (pinfunction "OUT_1") (pintype "passive"))
    )
    (net (code "46") (name "Net-(S7-OUT)") (class "Default")
      (node (ref "R13") (pin "1") (pinfunction "1_1") (pintype "passive"))
      (node (ref "S7") (pin "1") (pinfunction "OUT_1") (pintype "passive"))
    )
    (net (code "47") (name "Net-(S8-OUT)") (class "Default")
      (node (ref "R14") (pin "1") (pinfunction "1_1") (pintype "passive"))
      (node (ref "S8") (pin "1") (pinfunction "OUT_1") (pintype "passive"))
    )
    (net (code "48") (name "Net-(S9-OUT)") (class "Default")
      (node (ref "R18") (pin "1") (pinfunction "1_1") (pintype "passive"))
      (node (ref "S9") (pin "1") (pinfunction "OUT_1") (pintype "passive"))
    )
    (net (code "49") (name "Net-(S10-OUT)") (class "Default")
      (node (ref "R20") (pin "1") (pinfunction "1_1") (pintype "passive"))
      (node (ref "S10") (pin "1") (pinfunction "OUT_1") (pintype "passive"))
    )
    (net (code "50") (name "Net-(S11-OUT)") (class "Default")
      (node (ref "R21") (pin "1") (pinfunction "1_1") (pintype "passive"))
      (node (ref "S11") (pin "1") (pinfunction "OUT_1") (pintype "passive"))
    )
    (net (code "51") (name "Net-(S12-OUT)") (class "Default")
      (node (ref "R24") (pin "1") (pinfunction "1_1") (pintype "passive"))
      (node (ref "S12") (pin "1") (pinfunction "OUT_1") (pintype "passive"))
    )
    (net (code "52") (name "Net-(S13-OUT)") (class "Default")
      (node (ref "R26") (pin "1") (pinfunction "1_1") (pintype "passive"))
      (node (ref "S13") (pin "1") (pinfunction "OUT_1") (pintype "passive"))
    )
    (net (code "53") (name "Net-(S14-OUT)") (class "Default")
      (node (ref "R27") (pin "1") (pinfunction "1_1") (pintype "passive"))
      (node (ref "S14") (pin "1") (pinfunction "OUT_1") (pintype "passive"))
    )
    (net (code "54") (name "Net-(S15-OUT)") (class "Default")
      (node (ref "R30") (pin "1") (pinfunction "1_1") (pintype "passive"))
      (node (ref "S15") (pin "1") (pinfunction "OUT_1") (pintype "passive"))
    )
    (net (code "55") (name "Net-(S16-OUT)") (class "Default")
      (node (ref "R32") (pin "1") (pinfunction "1_1") (pintype "passive"))
      (node (ref "S16") (pin "1") (pinfunction "OUT_1") (pintype "passive"))
    )
    (net (code "56") (name "unconnected-(MPU6050-Pad5)") (class "Default")
      (node (ref "MPU6050") (pin "5") (pinfunction "5_5") (pintype "passive+no_connect"))
    )
    (net (code "57") (name "unconnected-(MPU6050-Pad6)") (class "Default")
      (node (ref "MPU6050") (pin "6") (pinfunction "6_6") (pintype "passive+no_connect"))
    )
    (net (code "58") (name "unconnected-(MPU6050-Pad7)") (class "Default")
      (node (ref "MPU6050") (pin "7") (pinfunction "7_7") (pintype "passive+no_connect"))
    )
    (net (code "59") (name "unconnected-(MPU6050-Pad8)") (class "Default")
      (node (ref "MPU6050") (pin "8") (pinfunction "8_8") (pintype "passive+no_connect"))
    )
  )
)
